# logic.net
KiCad netlist of a schematic drawn in EAGLE
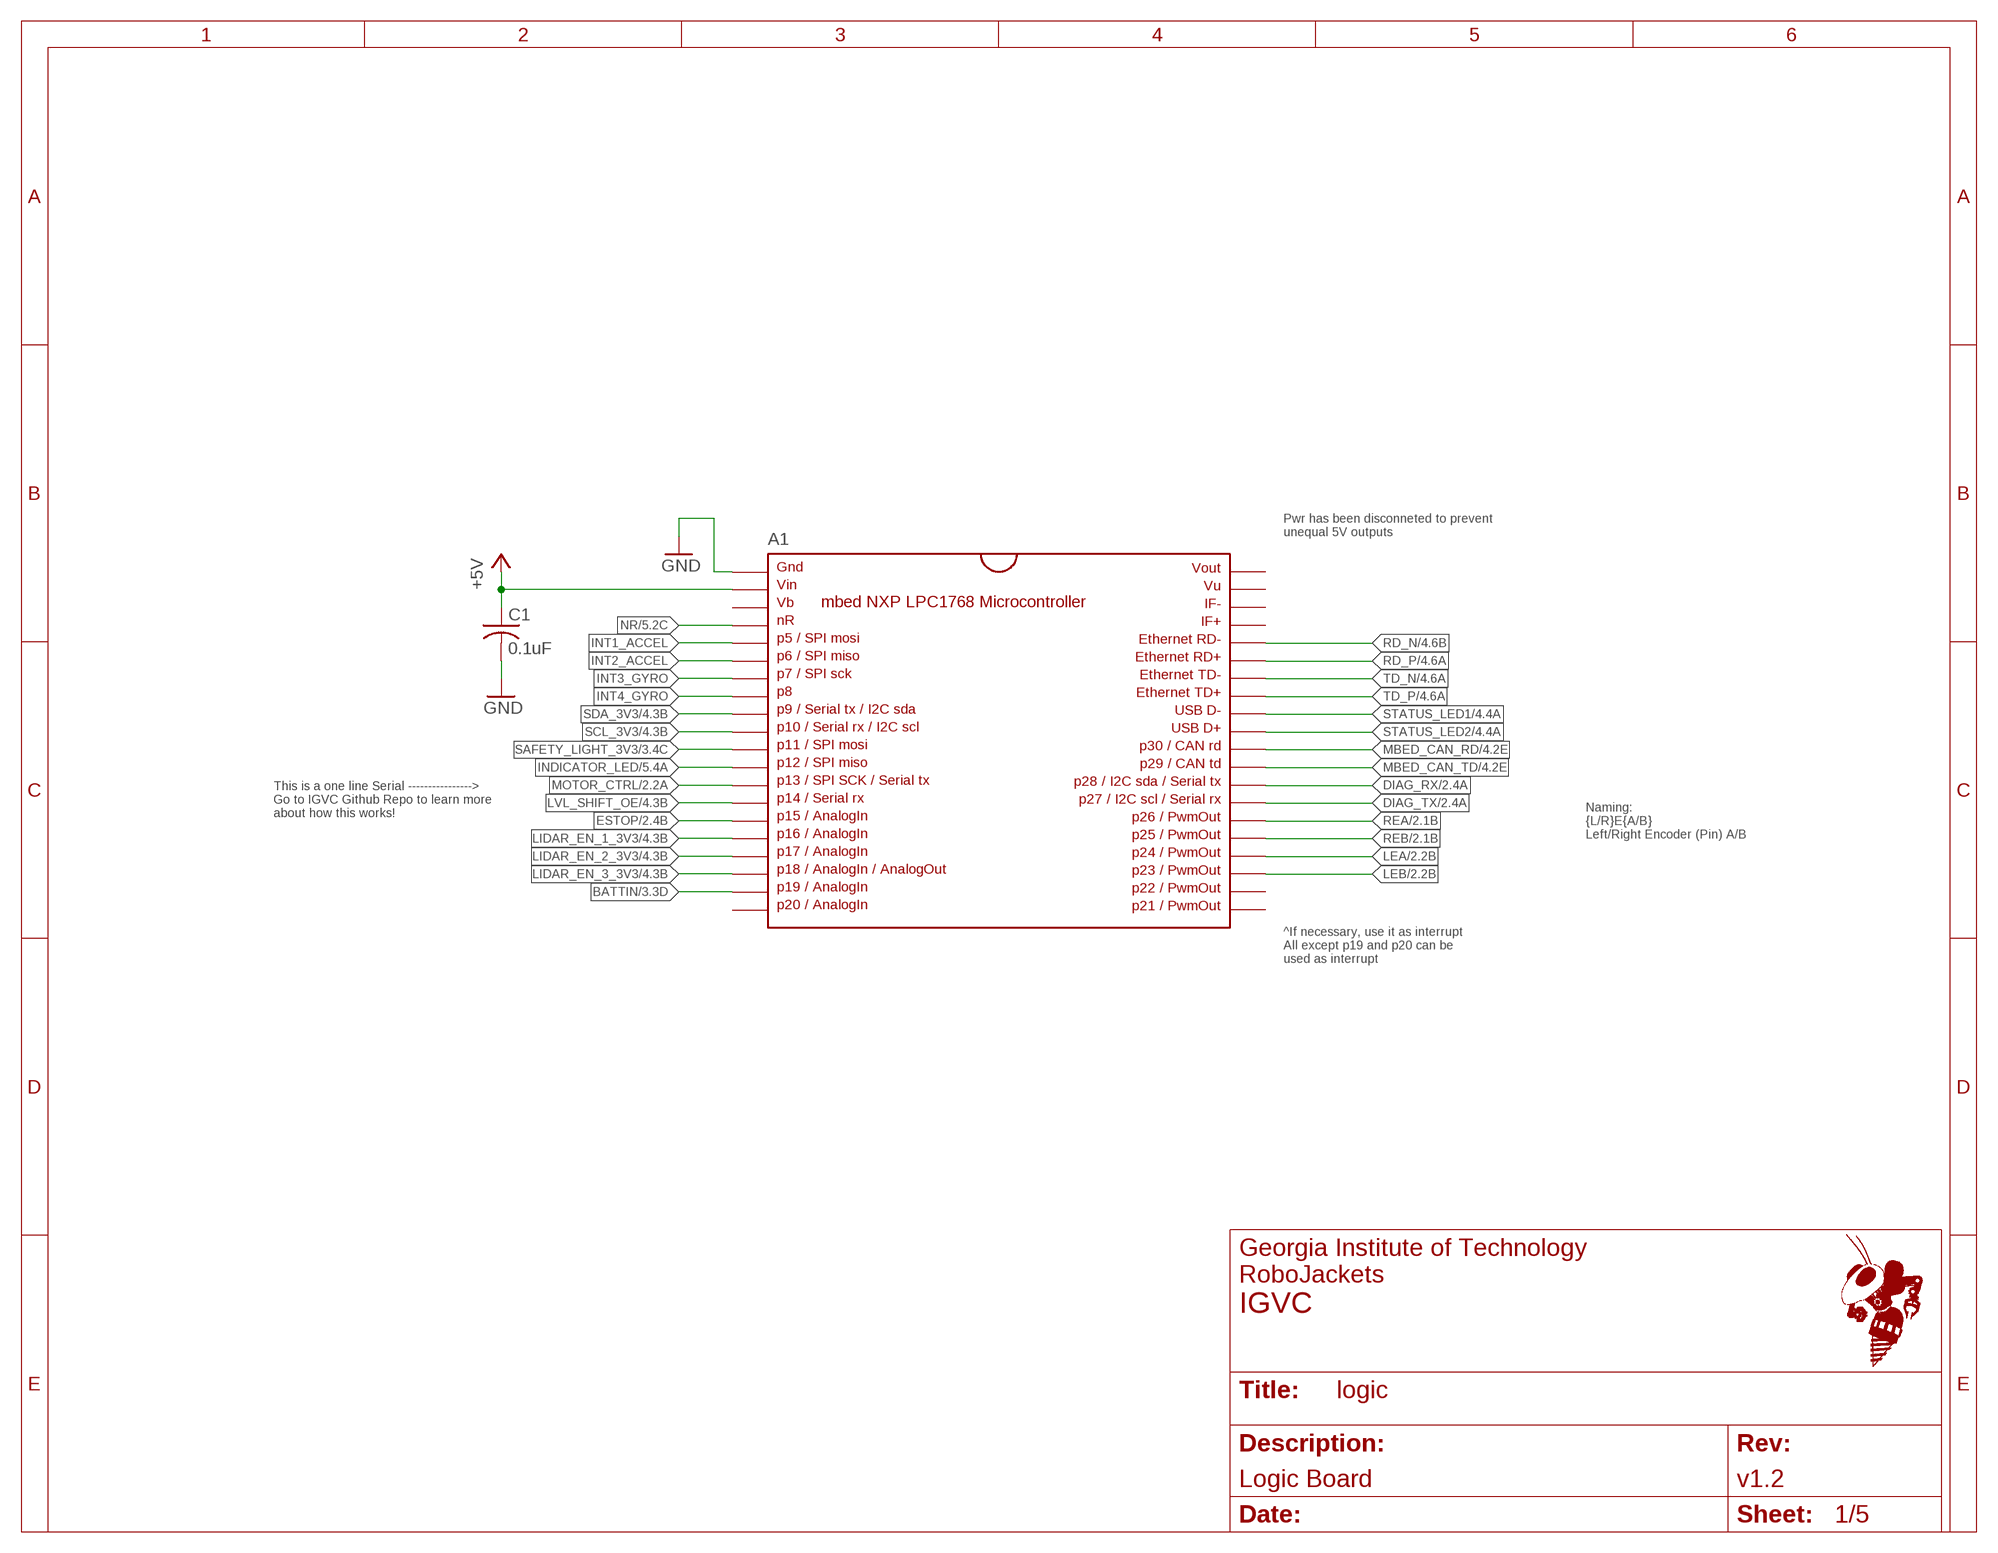
[diagram p0: schematic, sheet 1]
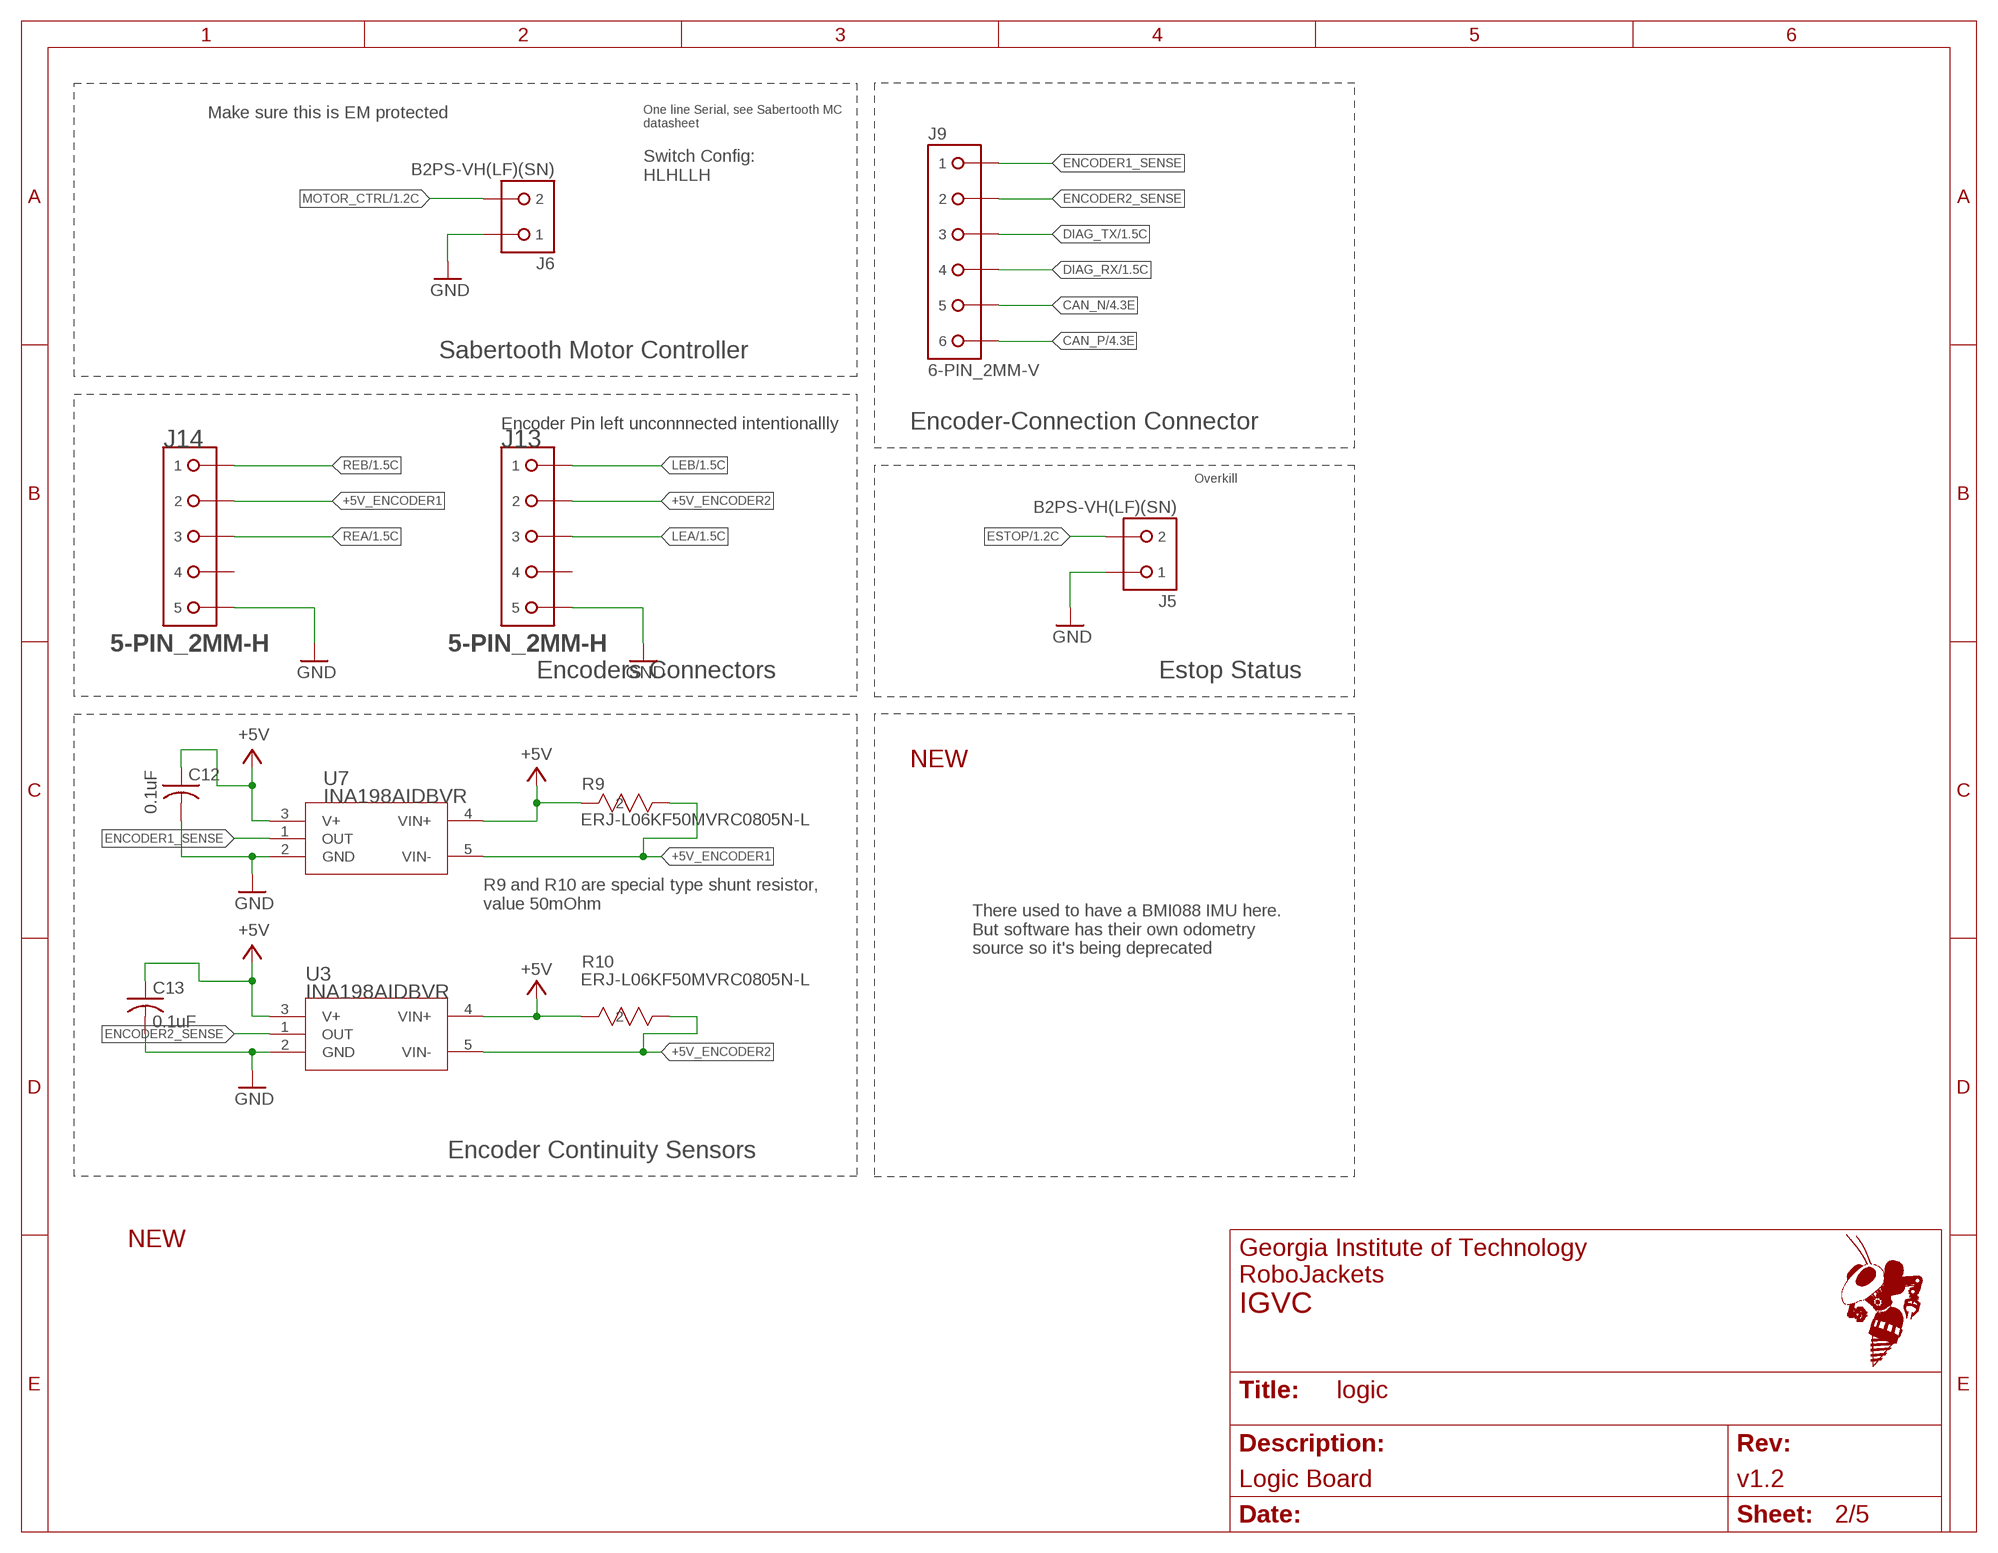
[diagram p1: schematic, sheet 2]
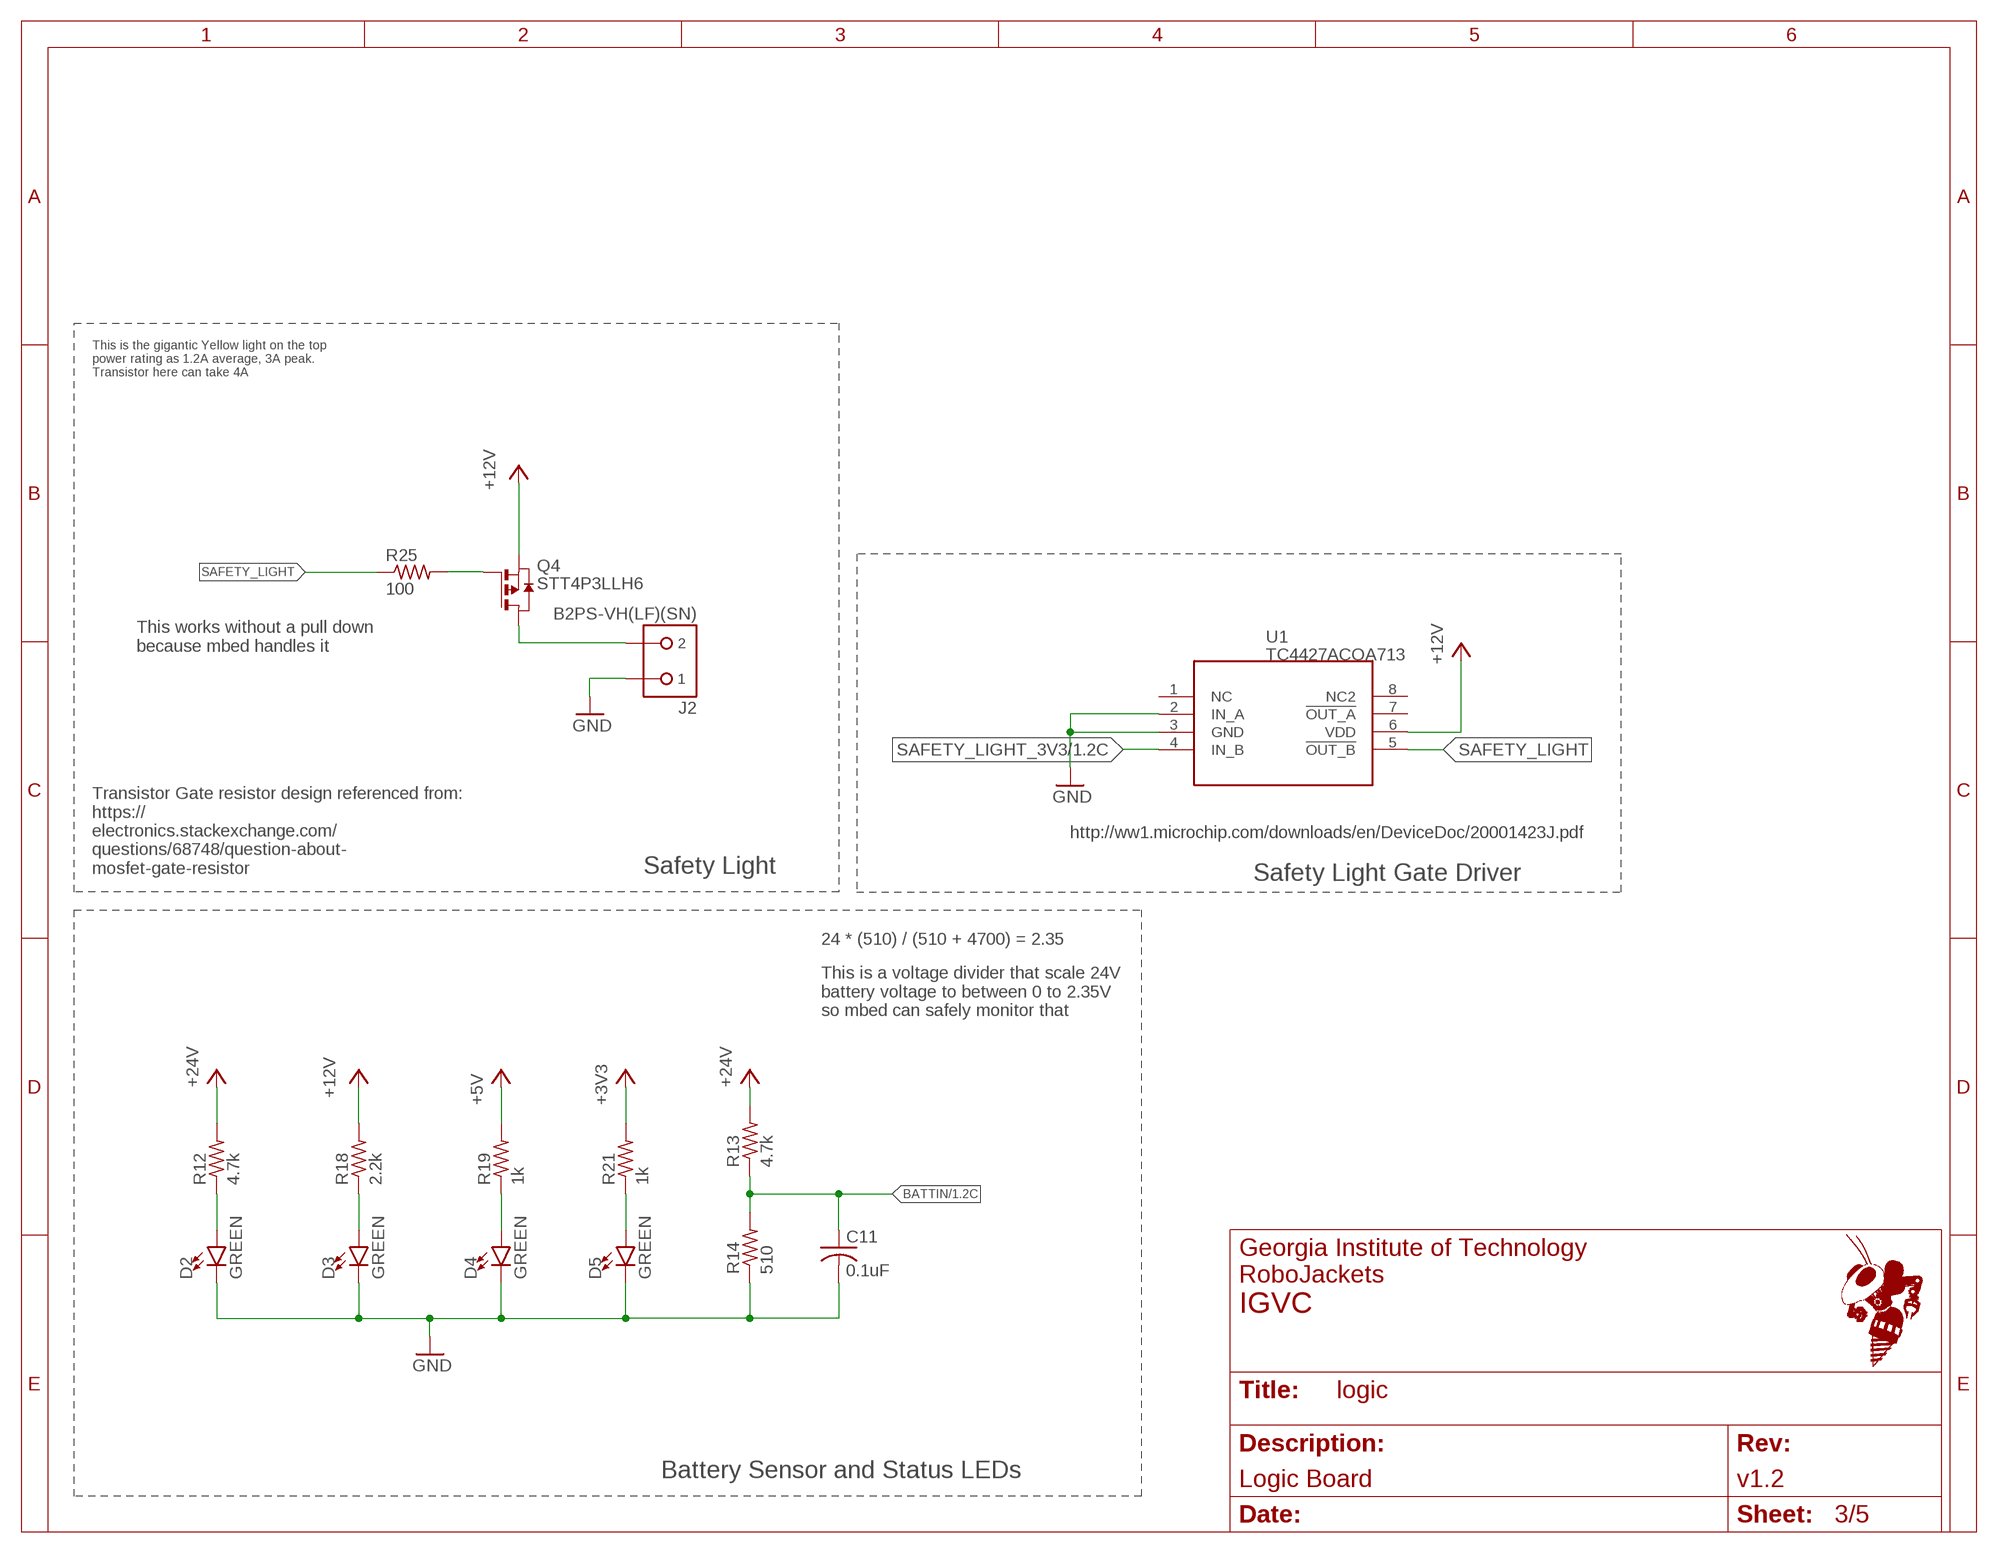
[diagram p2: schematic, sheet 3]
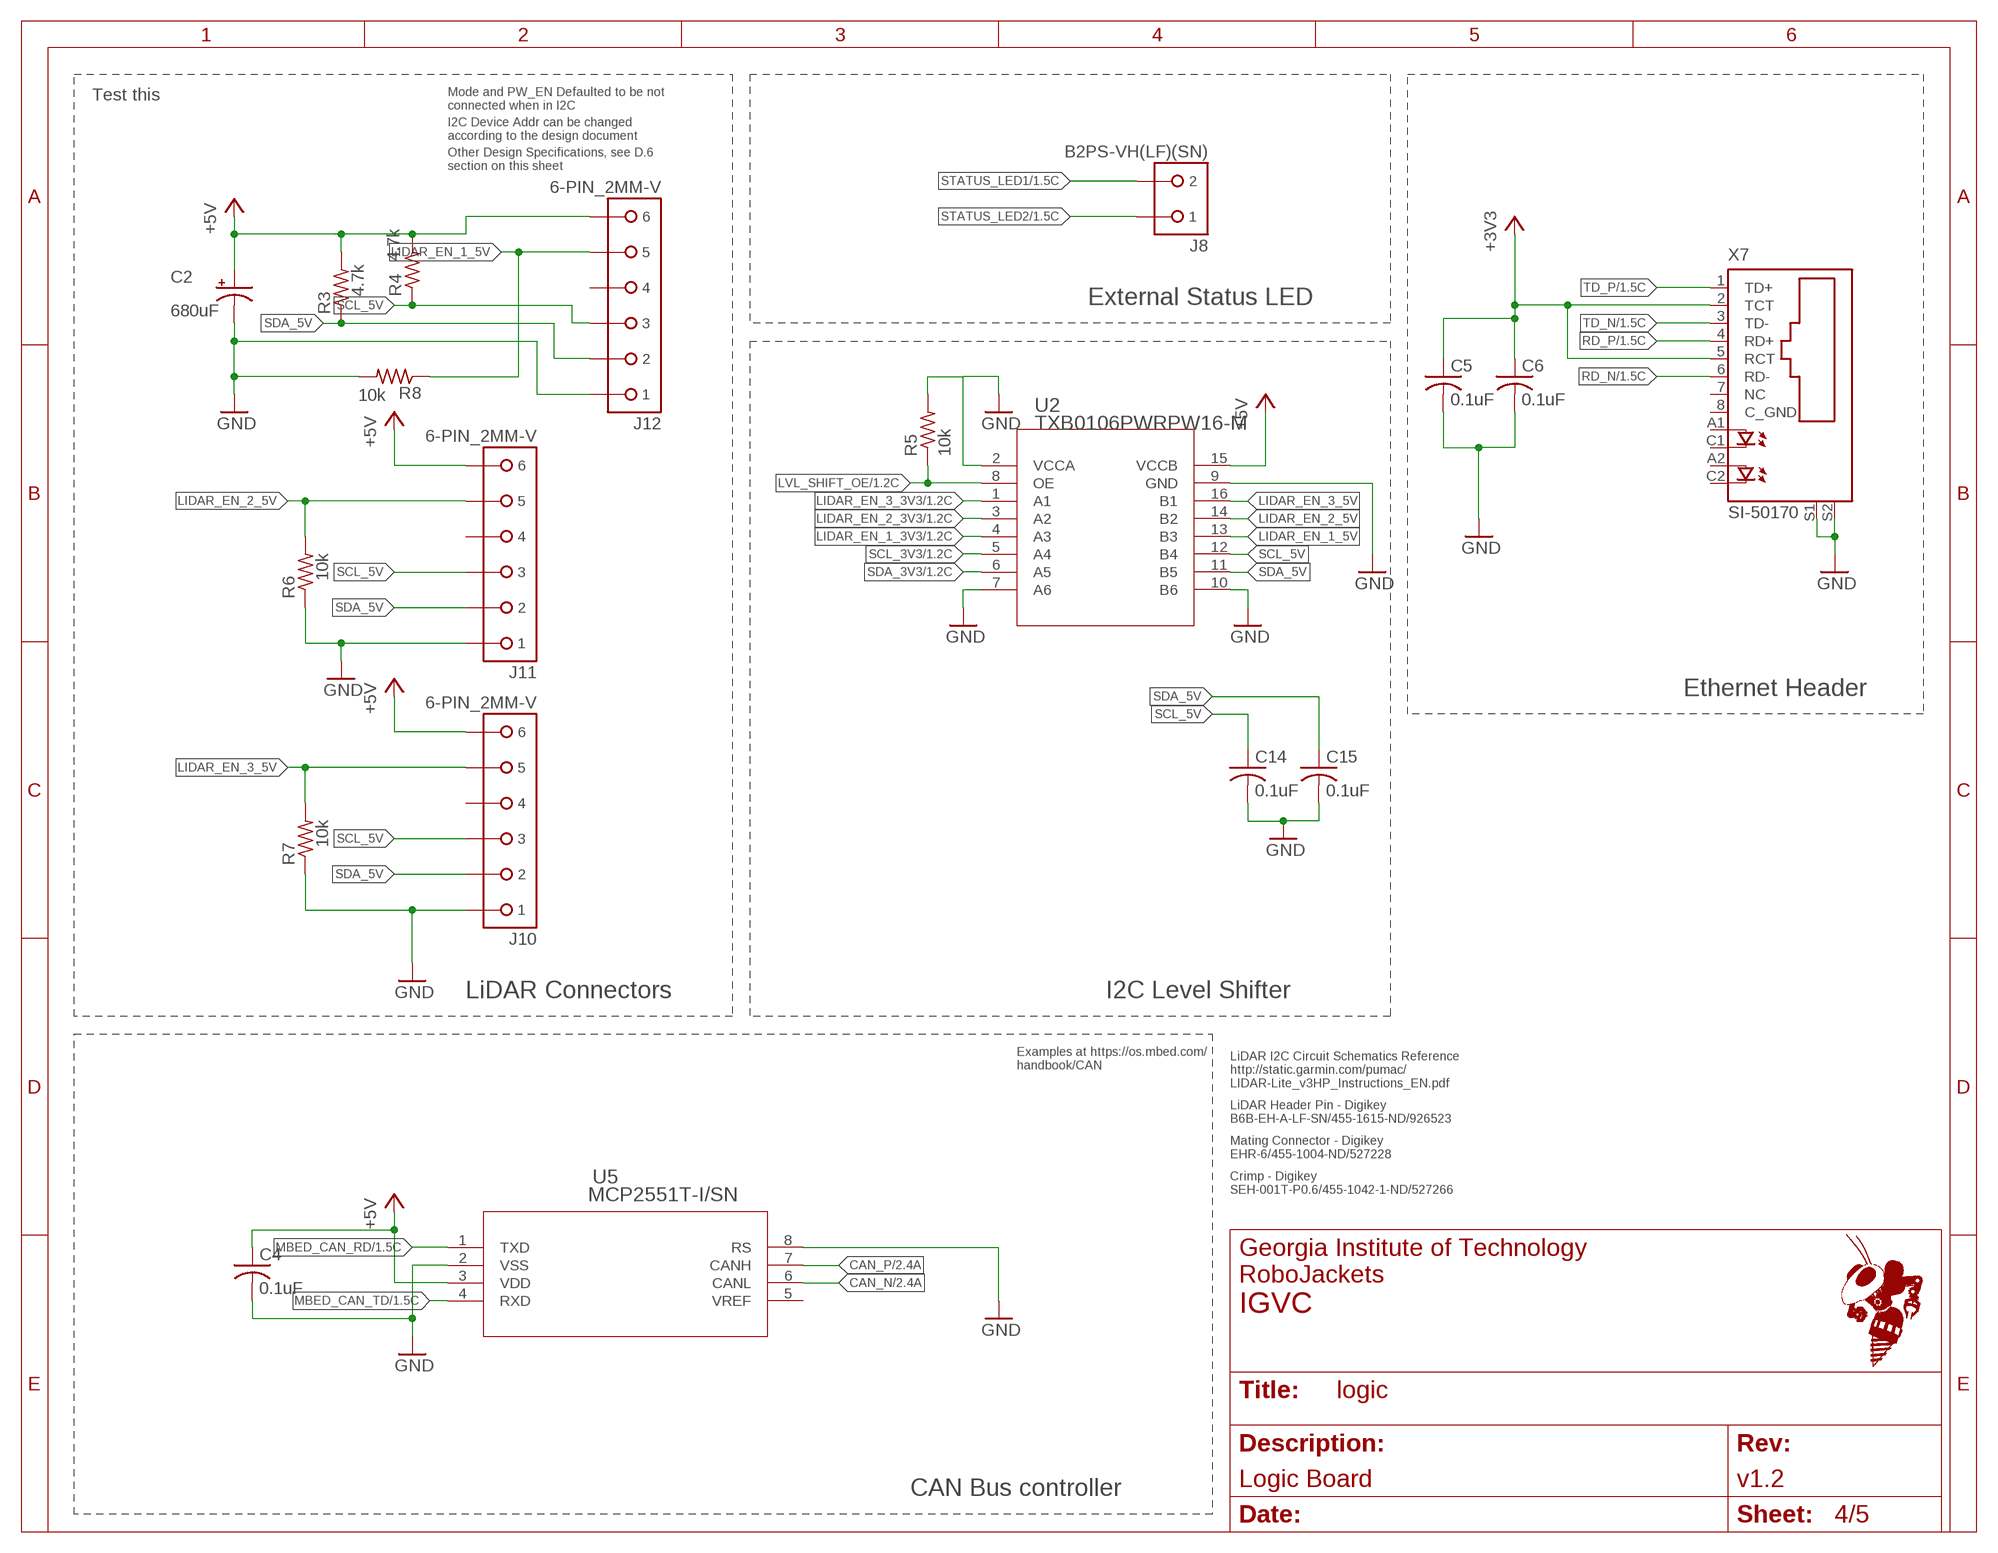
[diagram p3: schematic, sheet 4]
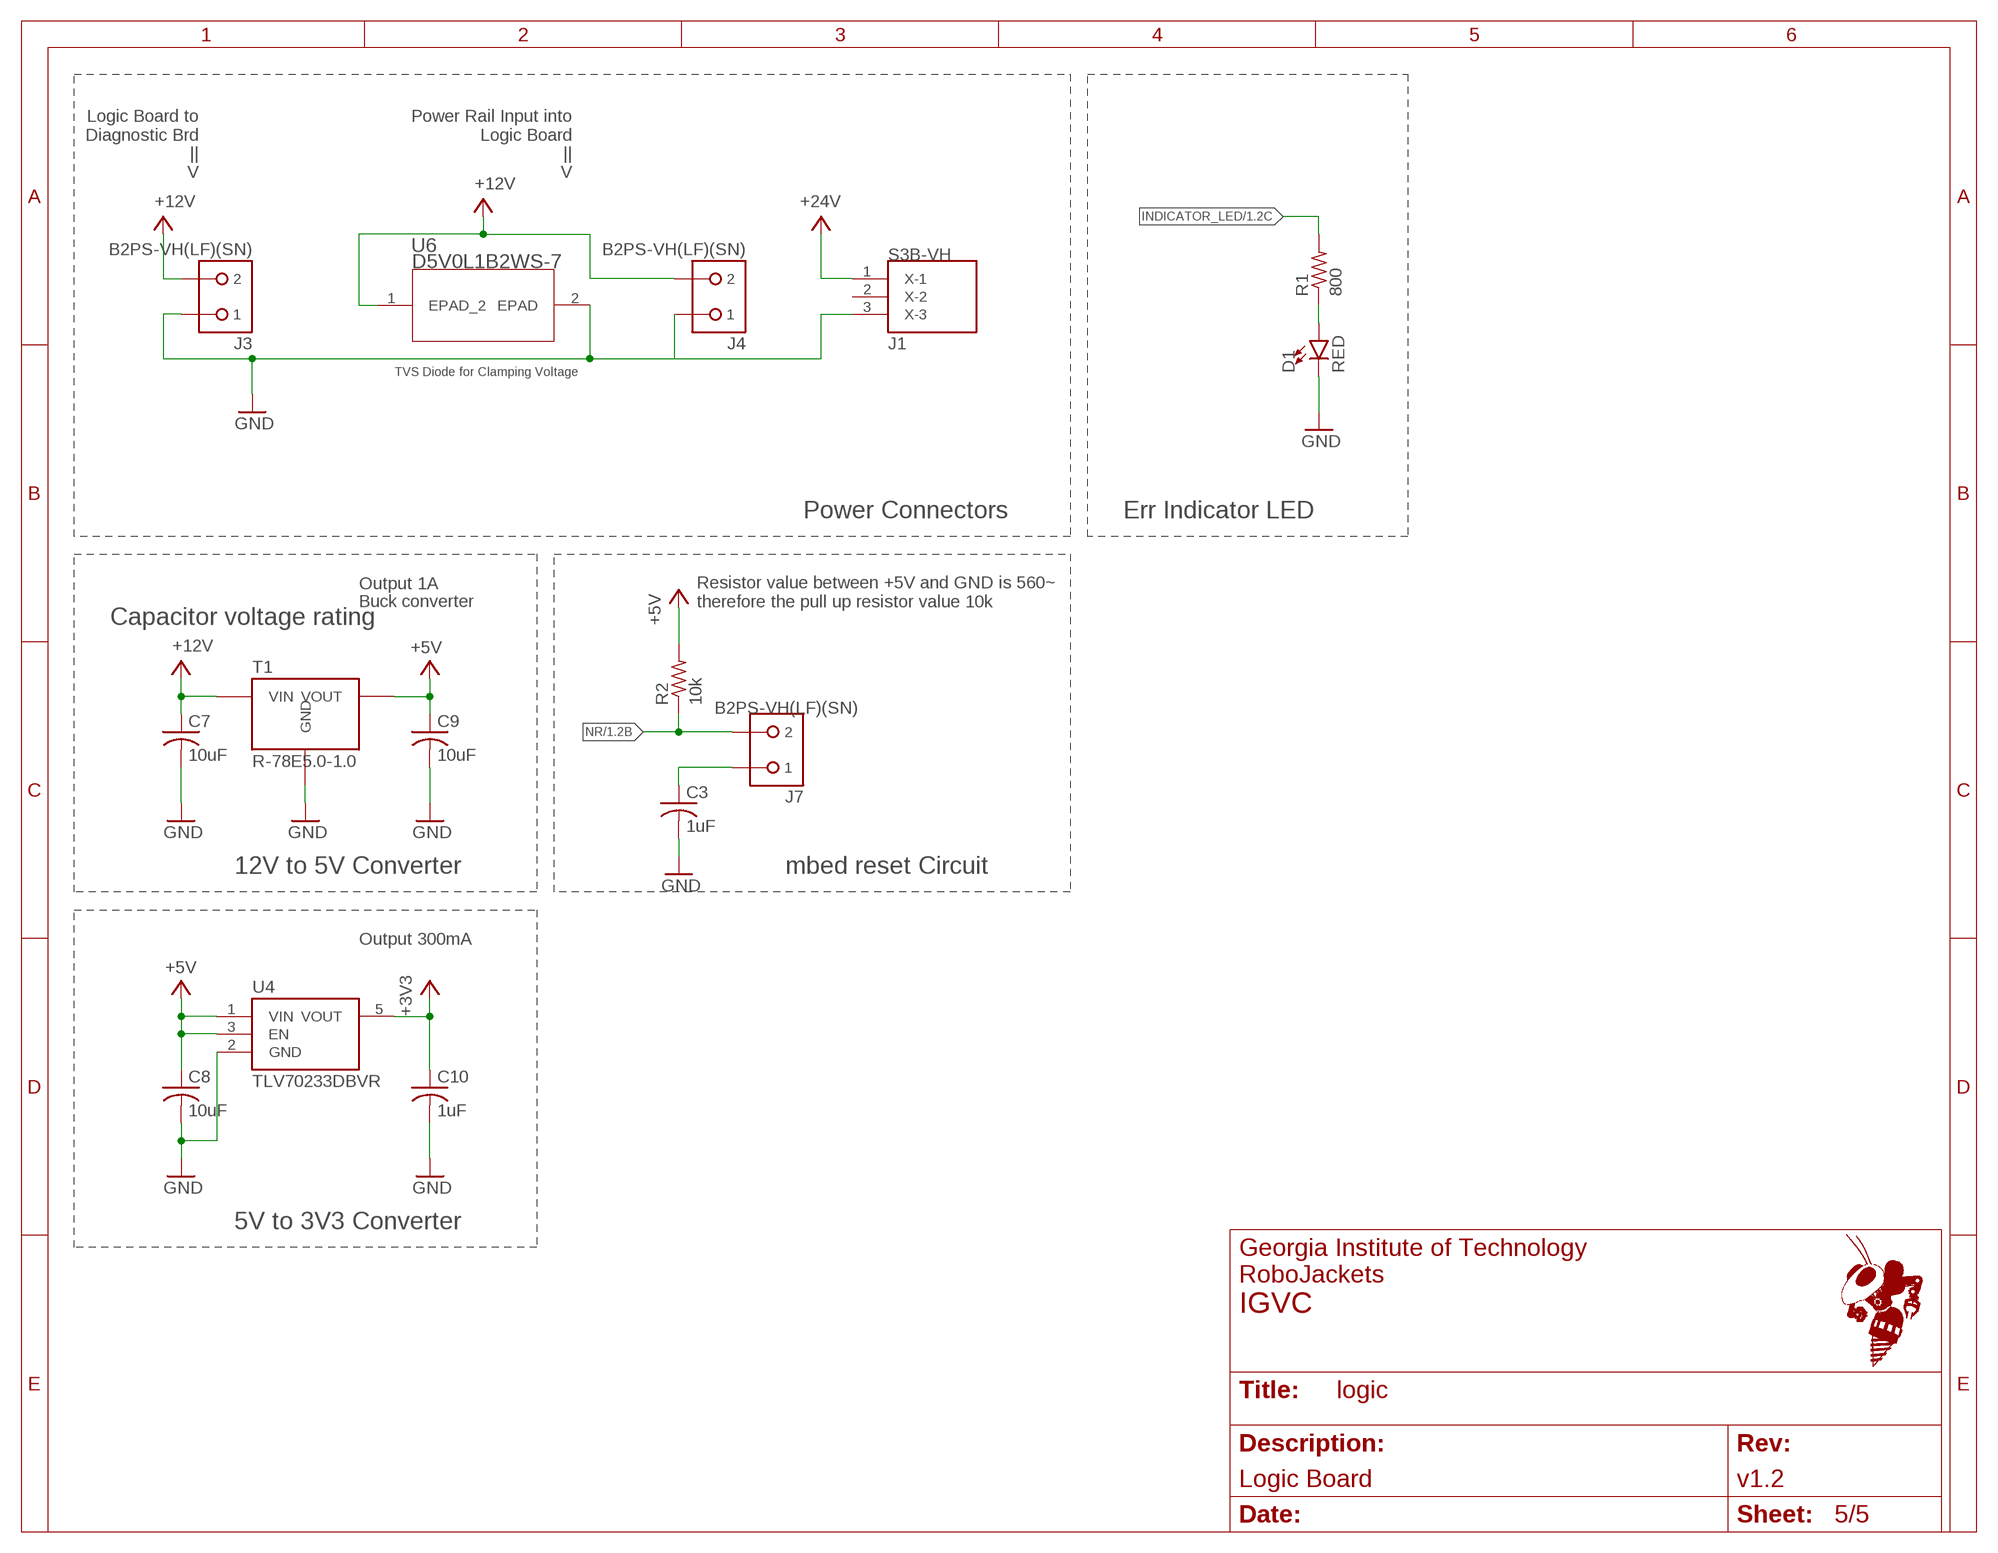
[diagram p4: schematic, sheet 5]

(export (version "E")
  (design (tool "Eeschema 10.0.6"))
  (components
    (comp (ref "A1")
      (value "MBED1768")
      (footprint "eagle-import:SPARKFUN-BOARDS_DIL40_0.9")
      (libsource (lib "eagle-import") (part "SPARKFUN-BOARDS_MBED_NXP_LPC1768"))
    )
    (comp (ref "C1")
      (value "0.1uF")
      (footprint "eagle-import:C0603")
      (libsource (lib "eagle-import") (part "C-USC0603"))
    )
    (comp (ref "C11")
      (value "0.1uF")
      (footprint "eagle-import:C0603")
      (libsource (lib "eagle-import") (part "C-USC0603"))
    )
    (comp (ref "D2")
      (value "GREEN")
      (footprint "eagle-import:LED-0603")
      (libsource (lib "eagle-import") (part "LED-BLUE0603"))
    )
    (comp (ref "D3")
      (value "GREEN")
      (footprint "eagle-import:LED-0603")
      (libsource (lib "eagle-import") (part "LED-BLUE0603"))
    )
    (comp (ref "D4")
      (value "GREEN")
      (footprint "eagle-import:LED-0603")
      (libsource (lib "eagle-import") (part "LED-GREEN0603"))
    )
    (comp (ref "D5")
      (value "GREEN")
      (footprint "eagle-import:LED-0603")
      (libsource (lib "eagle-import") (part "LED-GREEN0603"))
    )
    (comp (ref "J2")
      (value "B2PS-VH(LF)(SN)")
      (footprint "eagle-import:B2PS-CENTERED")
      (libsource (lib "eagle-import") (part "B2P?-VH(LF)(SN)S"))
    )
    (comp (ref "Q4")
      (value "STT4P3LLH6")
      (footprint "eagle-import:SOT23-6")
      (libsource (lib "eagle-import") (part "STT4P3LLH6"))
    )
    (comp (ref "R12")
      (value "4.7k")
      (footprint "eagle-import:R0603")
      (libsource (lib "eagle-import") (part "R-US_R0603"))
    )
    (comp (ref "R13")
      (value "4.7k")
      (footprint "eagle-import:R0603")
      (libsource (lib "eagle-import") (part "R-US_R0603"))
    )
    (comp (ref "R14")
      (value "510")
      (footprint "eagle-import:R0603")
      (libsource (lib "eagle-import") (part "R-US_R0603"))
    )
    (comp (ref "R18")
      (value "2.2k")
      (footprint "eagle-import:R0603")
      (libsource (lib "eagle-import") (part "R-US_R0603"))
    )
    (comp (ref "R19")
      (value "1k")
      (footprint "eagle-import:R0603")
      (libsource (lib "eagle-import") (part "R-US_R0603"))
    )
    (comp (ref "R21")
      (value "1k")
      (footprint "eagle-import:R0603")
      (libsource (lib "eagle-import") (part "R-US_R0603"))
    )
    (comp (ref "R25")
      (value "100")
      (footprint "eagle-import:R0603")
      (libsource (lib "eagle-import") (part "R-US_R0603"))
    )
    (comp (ref "U1")
      (value "TC4427ACOA713")
      (footprint "eagle-import:SOIC-8")
      (libsource (lib "eagle-import") (part "TC4427ACOA713"))
    )
    (comp (ref "C12")
      (value "0.1uF")
      (footprint "eagle-import:C0603")
      (libsource (lib "eagle-import") (part "C-USC0603"))
    )
    (comp (ref "C13")
      (value "0.1uF")
      (footprint "eagle-import:C0603")
      (libsource (lib "eagle-import") (part "C-USC0603"))
    )
    (comp (ref "J5")
      (value "B2PS-VH(LF)(SN)")
      (footprint "eagle-import:B2PS-CENTERED")
      (libsource (lib "eagle-import") (part "B2P?-VH(LF)(SN)S"))
    )
    (comp (ref "J6")
      (value "B2PS-VH(LF)(SN)")
      (footprint "eagle-import:B2PS-CENTERED")
      (libsource (lib "eagle-import") (part "B2P?-VH(LF)(SN)S"))
    )
    (comp (ref "J9")
      (value "6-PIN_2MM-V")
      (footprint "eagle-import:2MM-6-V")
      (libsource (lib "eagle-import") (part "6-PIN_2MM-V"))
    )
    (comp (ref "J13")
      (value "5-PIN_2MM-H")
      (footprint "eagle-import:2MM-5-H")
      (libsource (lib "eagle-import") (part "5-PIN_2MM-H"))
    )
    (comp (ref "J14")
      (value "5-PIN_2MM-H")
      (footprint "eagle-import:2MM-5-H")
      (libsource (lib "eagle-import") (part "5-PIN_2MM-H"))
    )
    (comp (ref "R9")
      (value "ERJ-L06KF50MVRC0805N-L")
      (footprint "eagle-import:RC0805N-L")
      (fields (field (name "MANUFACTURER_PART_NUMBER") "ERJL06KF50MV"))
      (libsource (lib "eagle-import") (part "ERJ-L06KF50MVRC0805N-L"))
    )
    (comp (ref "R10")
      (value "ERJ-L06KF50MVRC0805N-L")
      (footprint "eagle-import:RC0805N-L")
      (fields (field (name "MANUFACTURER_PART_NUMBER") "ERJL06KF50MV"))
      (libsource (lib "eagle-import") (part "ERJ-L06KF50MVRC0805N-L"))
    )
    (comp (ref "U3")
      (value "INA198AIDBVR")
      (footprint "eagle-import:DBV5")
      (libsource (lib "eagle-import") (part "INA198AIDBVR"))
    )
    (comp (ref "U7")
      (value "INA198AIDBVR")
      (footprint "eagle-import:DBV5")
      (libsource (lib "eagle-import") (part "INA198AIDBVR"))
    )
    (comp (ref "C2")
      (value "680uF")
      (footprint "eagle-import:E5-5")
      (libsource (lib "eagle-import") (part "CPOL-USE5-5"))
    )
    (comp (ref "C4")
      (value "0.1uF")
      (footprint "eagle-import:C0603")
      (libsource (lib "eagle-import") (part "C-USC0603"))
    )
    (comp (ref "C5")
      (value "0.1uF")
      (footprint "eagle-import:C0603")
      (libsource (lib "eagle-import") (part "C-USC0603"))
    )
    (comp (ref "C6")
      (value "0.1uF")
      (footprint "eagle-import:C0603")
      (libsource (lib "eagle-import") (part "C-USC0603"))
    )
    (comp (ref "C14")
      (value "0.1uF")
      (footprint "eagle-import:C0603")
      (libsource (lib "eagle-import") (part "C-USC0603"))
    )
    (comp (ref "C15")
      (value "0.1uF")
      (footprint "eagle-import:C0603")
      (libsource (lib "eagle-import") (part "C-USC0603"))
    )
    (comp (ref "J8")
      (value "B2PS-VH(LF)(SN)")
      (footprint "eagle-import:B2PS-CENTERED")
      (libsource (lib "eagle-import") (part "B2P?-VH(LF)(SN)S"))
    )
    (comp (ref "J10")
      (value "6-PIN_2MM-V")
      (footprint "eagle-import:2MM-6-V")
      (libsource (lib "eagle-import") (part "6-PIN_2MM-V"))
    )
    (comp (ref "J11")
      (value "6-PIN_2MM-V")
      (footprint "eagle-import:2MM-6-V")
      (libsource (lib "eagle-import") (part "6-PIN_2MM-V"))
    )
    (comp (ref "J12")
      (value "6-PIN_2MM-V")
      (footprint "eagle-import:2MM-6-V")
      (libsource (lib "eagle-import") (part "6-PIN_2MM-V"))
    )
    (comp (ref "R3")
      (value "4.7k")
      (footprint "eagle-import:R0603")
      (libsource (lib "eagle-import") (part "R-US_R0603"))
    )
    (comp (ref "R4")
      (value "4.7k")
      (footprint "eagle-import:R0603")
      (libsource (lib "eagle-import") (part "R-US_R0603"))
    )
    (comp (ref "R5")
      (value "10k")
      (footprint "eagle-import:R0603")
      (libsource (lib "eagle-import") (part "R-US_R0603"))
    )
    (comp (ref "R6")
      (value "10k")
      (footprint "eagle-import:R0603")
      (libsource (lib "eagle-import") (part "R-US_R0603"))
    )
    (comp (ref "R7")
      (value "10k")
      (footprint "eagle-import:R0603")
      (libsource (lib "eagle-import") (part "R-US_R0603"))
    )
    (comp (ref "R8")
      (value "10k")
      (footprint "eagle-import:R0603")
      (libsource (lib "eagle-import") (part "R-US_R0603"))
    )
    (comp (ref "U2")
      (value "TXB0106PWRPW16-M")
      (footprint "eagle-import:PW16-M")
      (fields (field (name "MANUFACTURER_PART_NUMBER") "TXB0106PWR"))
      (libsource (lib "eagle-import") (part "TXB0106PWRPW16-M"))
    )
    (comp (ref "U5")
      (value "MCP2551T-I/SN")
      (footprint "eagle-import:SOIC8-N_MC")
      (fields (field (name "MANUFACTURER_PART_NUMBER") "MCP2551TISN"))
      (libsource (lib "eagle-import") (part "MCP2551T-I/SN"))
    )
    (comp (ref "X7")
      (value "SI-50170")
      (footprint "eagle-import:SI-50170")
      (libsource (lib "eagle-import") (part "SI-50170"))
    )
    (comp (ref "C3")
      (value "1uF")
      (footprint "eagle-import:C0805")
      (libsource (lib "eagle-import") (part "C-USC0805"))
    )
    (comp (ref "C7")
      (value "10uF")
      (footprint "eagle-import:C0805")
      (libsource (lib "eagle-import") (part "C-USC0805"))
    )
    (comp (ref "C8")
      (value "10uF")
      (footprint "eagle-import:C0805")
      (libsource (lib "eagle-import") (part "C-USC0805"))
    )
    (comp (ref "C9")
      (value "10uF")
      (footprint "eagle-import:C0805")
      (libsource (lib "eagle-import") (part "C-USC0805"))
    )
    (comp (ref "C10")
      (value "1uF")
      (footprint "eagle-import:C0805")
      (libsource (lib "eagle-import") (part "C-USC0805"))
    )
    (comp (ref "D1")
      (value "RED")
      (footprint "eagle-import:LED-0603")
      (libsource (lib "eagle-import") (part "LED-BLUE0603"))
    )
    (comp (ref "J1")
      (value "S3B-VH")
      (footprint "eagle-import:S3B-VH")
      (libsource (lib "eagle-import") (part "S3B-VH"))
    )
    (comp (ref "J3")
      (value "B2PS-VH(LF)(SN)")
      (footprint "eagle-import:B2PS-CENTERED")
      (libsource (lib "eagle-import") (part "B2P?-VH(LF)(SN)S"))
    )
    (comp (ref "J4")
      (value "B2PS-VH(LF)(SN)")
      (footprint "eagle-import:B2PS-CENTERED")
      (libsource (lib "eagle-import") (part "B2P?-VH(LF)(SN)S"))
    )
    (comp (ref "J7")
      (value "B2PS-VH(LF)(SN)")
      (footprint "eagle-import:B2PS-CENTERED")
      (libsource (lib "eagle-import") (part "B2P?-VH(LF)(SN)S"))
    )
    (comp (ref "R1")
      (value "800")
      (footprint "eagle-import:R0603")
      (libsource (lib "eagle-import") (part "R-US_R0603"))
    )
    (comp (ref "R2")
      (value "10k")
      (footprint "eagle-import:R0603")
      (libsource (lib "eagle-import") (part "R-US_R0603"))
    )
    (comp (ref "T1")
      (value "R-78E5.0-1.0")
      (footprint "eagle-import:R-78E")
      (libsource (lib "eagle-import") (part "R-78E5.0-1.0"))
    )
    (comp (ref "U4")
      (value "TLV70233DBVR")
      (footprint "eagle-import:SOT-23-5")
      (libsource (lib "eagle-import") (part "TLV70233DBVR"))
    )
    (comp (ref "U6")
      (value "D5V0L1B2WS-7")
      (footprint "eagle-import:SOD323")
      (libsource (lib "eagle-import") (part "D5V0L1B2WS-7"))
    )
  )
  (nets
    (net (code "1") (name "+3V3") (class "Default")
      (node (ref "C10") (pin "1") (pinfunction "1_1") (pintype "passive"))
      (node (ref "C5") (pin "1") (pinfunction "1_1") (pintype "passive"))
      (node (ref "C6") (pin "1") (pinfunction "1_1") (pintype "passive"))
      (node (ref "R21") (pin "2") (pinfunction "2_2") (pintype "passive"))
      (node (ref "U4") (pin "5") (pinfunction "VOUT_5") (pintype "bidirectional"))
      (node (ref "X7") (pin "2") (pinfunction "TCT_2") (pintype "passive"))
      (node (ref "X7") (pin "5") (pinfunction "RCT_5") (pintype "passive"))
    )
    (net (code "2") (name "+5V") (class "Default")
      (node (ref "A1") (pin "2") (pinfunction "P$2_2") (pintype "bidirectional"))
      (node (ref "C1") (pin "1") (pinfunction "1_1") (pintype "passive"))
      (node (ref "C12") (pin "1") (pinfunction "1_1") (pintype "passive"))
      (node (ref "C13") (pin "1") (pinfunction "1_1") (pintype "passive"))
      (node (ref "C2") (pin "+") (pinfunction "+_+") (pintype "passive"))
      (node (ref "C4") (pin "1") (pinfunction "1_1") (pintype "passive"))
      (node (ref "C8") (pin "1") (pinfunction "1_1") (pintype "passive"))
      (node (ref "C9") (pin "1") (pinfunction "1_1") (pintype "passive"))
      (node (ref "J10") (pin "6") (pinfunction "6_6") (pintype "passive"))
      (node (ref "J11") (pin "6") (pinfunction "6_6") (pintype "passive"))
      (node (ref "J12") (pin "6") (pinfunction "6_6") (pintype "passive"))
      (node (ref "R10") (pin "2") (pinfunction "2_2") (pintype "passive"))
      (node (ref "R19") (pin "2") (pinfunction "2_2") (pintype "passive"))
      (node (ref "R2") (pin "2") (pinfunction "2_2") (pintype "passive"))
      (node (ref "R3") (pin "2") (pinfunction "2_2") (pintype "passive"))
      (node (ref "R4") (pin "2") (pinfunction "2_2") (pintype "passive"))
      (node (ref "R9") (pin "2") (pinfunction "2_2") (pintype "passive"))
      (node (ref "T1") (pin "3") (pinfunction "VOUT_3") (pintype "bidirectional"))
      (node (ref "U2") (pin "15") (pinfunction "VCCB_15") (pintype "power_in"))
      (node (ref "U3") (pin "3") (pinfunction "V+_3") (pintype "power_in"))
      (node (ref "U3") (pin "4") (pinfunction "VIN+_4") (pintype "input"))
      (node (ref "U4") (pin "1") (pinfunction "VIN_1") (pintype "bidirectional"))
      (node (ref "U4") (pin "3") (pinfunction "EN_3") (pintype "bidirectional"))
      (node (ref "U5") (pin "3") (pinfunction "VDD_3") (pintype "passive"))
      (node (ref "U7") (pin "3") (pinfunction "V+_3") (pintype "power_in"))
      (node (ref "U7") (pin "4") (pinfunction "VIN+_4") (pintype "input"))
    )
    (net (code "3") (name "+5V_ENCODER1") (class "Default")
      (node (ref "J14") (pin "2") (pinfunction "2_2") (pintype "passive"))
      (node (ref "R9") (pin "1") (pinfunction "1_1") (pintype "passive"))
      (node (ref "U7") (pin "5") (pinfunction "VIN-_5") (pintype "input"))
    )
    (net (code "4") (name "+5V_ENCODER2") (class "Default")
      (node (ref "J13") (pin "2") (pinfunction "2_2") (pintype "passive"))
      (node (ref "R10") (pin "1") (pinfunction "1_1") (pintype "passive"))
      (node (ref "U3") (pin "5") (pinfunction "VIN-_5") (pintype "input"))
    )
    (net (code "5") (name "+12V") (class "Default")
      (node (ref "C7") (pin "1") (pinfunction "1_1") (pintype "passive"))
      (node (ref "J3") (pin "2") (pinfunction "2_2") (pintype "bidirectional"))
      (node (ref "J4") (pin "2") (pinfunction "2_2") (pintype "bidirectional"))
      (node (ref "Q4") (pin "4") (pinfunction "S_4") (pintype "passive"))
      (node (ref "R18") (pin "2") (pinfunction "2_2") (pintype "passive"))
      (node (ref "T1") (pin "1") (pinfunction "VIN_1") (pintype "bidirectional"))
      (node (ref "U1") (pin "6") (pinfunction "VDD_6") (pintype "bidirectional"))
      (node (ref "U6") (pin "1") (pinfunction "EPAD_2_1") (pintype "passive"))
    )
    (net (code "6") (name "+24V") (class "Default")
      (node (ref "J1") (pin "1") (pinfunction "X-1_1") (pintype "bidirectional"))
      (node (ref "R12") (pin "2") (pinfunction "2_2") (pintype "passive"))
      (node (ref "R13") (pin "2") (pinfunction "2_2") (pintype "passive"))
    )
    (net (code "7") (name "BATTIN") (class "Default")
      (node (ref "A1") (pin "19") (pinfunction "P$19_19") (pintype "bidirectional"))
      (node (ref "C11") (pin "1") (pinfunction "1_1") (pintype "passive"))
      (node (ref "R13") (pin "1") (pinfunction "1_1") (pintype "passive"))
      (node (ref "R14") (pin "2") (pinfunction "2_2") (pintype "passive"))
    )
    (net (code "8") (name "CAN_N") (class "Default")
      (node (ref "J9") (pin "5") (pinfunction "5_5") (pintype "passive"))
      (node (ref "U5") (pin "6") (pinfunction "CANL_6") (pintype "passive"))
    )
    (net (code "9") (name "CAN_P") (class "Default")
      (node (ref "J9") (pin "6") (pinfunction "6_6") (pintype "passive"))
      (node (ref "U5") (pin "7") (pinfunction "CANH_7") (pintype "passive"))
    )
    (net (code "10") (name "DIAG_RX") (class "Default")
      (node (ref "A1") (pin "28") (pinfunction "P$28_28") (pintype "bidirectional"))
      (node (ref "J9") (pin "4") (pinfunction "4_4") (pintype "passive"))
    )
    (net (code "11") (name "DIAG_TX") (class "Default")
      (node (ref "A1") (pin "27") (pinfunction "P$27_27") (pintype "bidirectional"))
      (node (ref "J9") (pin "3") (pinfunction "3_3") (pintype "passive"))
    )
    (net (code "12") (name "ENCODER1_SENSE") (class "Default")
      (node (ref "J9") (pin "1") (pinfunction "1_1") (pintype "passive"))
      (node (ref "U7") (pin "1") (pinfunction "OUT_1") (pintype "output"))
    )
    (net (code "13") (name "ENCODER2_SENSE") (class "Default")
      (node (ref "J9") (pin "2") (pinfunction "2_2") (pintype "passive"))
      (node (ref "U3") (pin "1") (pinfunction "OUT_1") (pintype "output"))
    )
    (net (code "14") (name "ESTOP") (class "Default")
      (node (ref "A1") (pin "15") (pinfunction "P$15_15") (pintype "bidirectional"))
      (node (ref "J5") (pin "2") (pinfunction "2_2") (pintype "bidirectional"))
    )
    (net (code "15") (name "GND") (class "Default")
      (node (ref "A1") (pin "1") (pinfunction "P$1_1") (pintype "bidirectional"))
      (node (ref "C1") (pin "2") (pinfunction "2_2") (pintype "passive"))
      (node (ref "C10") (pin "2") (pinfunction "2_2") (pintype "passive"))
      (node (ref "C11") (pin "2") (pinfunction "2_2") (pintype "passive"))
      (node (ref "C12") (pin "2") (pinfunction "2_2") (pintype "passive"))
      (node (ref "C13") (pin "2") (pinfunction "2_2") (pintype "passive"))
      (node (ref "C14") (pin "2") (pinfunction "2_2") (pintype "passive"))
      (node (ref "C15") (pin "2") (pinfunction "2_2") (pintype "passive"))
      (node (ref "C2") (pin "-") (pinfunction "-_-") (pintype "passive"))
      (node (ref "C3") (pin "2") (pinfunction "2_2") (pintype "passive"))
      (node (ref "C4") (pin "2") (pinfunction "2_2") (pintype "passive"))
      (node (ref "C5") (pin "2") (pinfunction "2_2") (pintype "passive"))
      (node (ref "C6") (pin "2") (pinfunction "2_2") (pintype "passive"))
      (node (ref "C7") (pin "2") (pinfunction "2_2") (pintype "passive"))
      (node (ref "C8") (pin "2") (pinfunction "2_2") (pintype "passive"))
      (node (ref "C9") (pin "2") (pinfunction "2_2") (pintype "passive"))
      (node (ref "D1") (pin "C") (pinfunction "C_C") (pintype "passive"))
      (node (ref "D2") (pin "C") (pinfunction "C_C") (pintype "passive"))
      (node (ref "D3") (pin "C") (pinfunction "C_C") (pintype "passive"))
      (node (ref "D4") (pin "C") (pinfunction "C_C") (pintype "passive"))
      (node (ref "D5") (pin "C") (pinfunction "C_C") (pintype "passive"))
      (node (ref "J1") (pin "3") (pinfunction "X-3_3") (pintype "bidirectional"))
      (node (ref "J10") (pin "1") (pinfunction "1_1") (pintype "passive"))
      (node (ref "J11") (pin "1") (pinfunction "1_1") (pintype "passive"))
      (node (ref "J12") (pin "1") (pinfunction "1_1") (pintype "passive"))
      (node (ref "J13") (pin "5") (pinfunction "5_5") (pintype "passive"))
      (node (ref "J14") (pin "5") (pinfunction "5_5") (pintype "passive"))
      (node (ref "J2") (pin "1") (pinfunction "1_1") (pintype "bidirectional"))
      (node (ref "J3") (pin "1") (pinfunction "1_1") (pintype "bidirectional"))
      (node (ref "J4") (pin "1") (pinfunction "1_1") (pintype "bidirectional"))
      (node (ref "J5") (pin "1") (pinfunction "1_1") (pintype "bidirectional"))
      (node (ref "J6") (pin "1") (pinfunction "1_1") (pintype "bidirectional"))
      (node (ref "R14") (pin "1") (pinfunction "1_1") (pintype "passive"))
      (node (ref "R5") (pin "2") (pinfunction "2_2") (pintype "passive"))
      (node (ref "R6") (pin "1") (pinfunction "1_1") (pintype "passive"))
      (node (ref "R7") (pin "1") (pinfunction "1_1") (pintype "passive"))
      (node (ref "R8") (pin "2") (pinfunction "2_2") (pintype "passive"))
      (node (ref "T1") (pin "2") (pinfunction "GND_2") (pintype "bidirectional"))
      (node (ref "U1") (pin "2") (pinfunction "IN_A_2") (pintype "bidirectional"))
      (node (ref "U1") (pin "3") (pinfunction "GND_3") (pintype "bidirectional"))
      (node (ref "U2") (pin "10") (pinfunction "B6_10") (pintype "bidirectional"))
      (node (ref "U2") (pin "2") (pinfunction "VCCA_2") (pintype "power_in"))
      (node (ref "U2") (pin "7") (pinfunction "A6_7") (pintype "bidirectional"))
      (node (ref "U2") (pin "9") (pinfunction "GND_9") (pintype "power_in"))
      (node (ref "U3") (pin "2") (pinfunction "GND_2") (pintype "power_in"))
      (node (ref "U4") (pin "2") (pinfunction "GND_2") (pintype "bidirectional"))
      (node (ref "U5") (pin "2") (pinfunction "VSS_2") (pintype "passive"))
      (node (ref "U5") (pin "8") (pinfunction "RS_8") (pintype "passive"))
      (node (ref "U6") (pin "2") (pinfunction "EPAD_2") (pintype "passive"))
      (node (ref "U7") (pin "2") (pinfunction "GND_2") (pintype "power_in"))
      (node (ref "X7") (pin "S1") (pinfunction "S1_S1") (pintype "passive"))
      (node (ref "X7") (pin "S2") (pinfunction "S2_S2") (pintype "passive"))
    )
    (net (code "16") (name "INDICATOR_LED") (class "Default")
      (node (ref "A1") (pin "12") (pinfunction "P$12_12") (pintype "bidirectional"))
      (node (ref "R1") (pin "2") (pinfunction "2_2") (pintype "passive"))
    )
    (net (code "17") (name "INT1_ACCEL") (class "Default")
      (node (ref "A1") (pin "5") (pinfunction "P$5_5") (pintype "bidirectional"))
    )
    (net (code "18") (name "INT2_ACCEL") (class "Default")
      (node (ref "A1") (pin "6") (pinfunction "P$6_6") (pintype "bidirectional"))
    )
    (net (code "19") (name "INT3_GYRO") (class "Default")
      (node (ref "A1") (pin "7") (pinfunction "P$7_7") (pintype "bidirectional"))
    )
    (net (code "20") (name "INT4_GYRO") (class "Default")
      (node (ref "A1") (pin "8") (pinfunction "P$8_8") (pintype "bidirectional"))
    )
    (net (code "21") (name "LEA") (class "Default")
      (node (ref "A1") (pin "24") (pinfunction "P$24_24") (pintype "bidirectional"))
      (node (ref "J13") (pin "3") (pinfunction "3_3") (pintype "passive"))
    )
    (net (code "22") (name "LEB") (class "Default")
      (node (ref "A1") (pin "23") (pinfunction "P$23_23") (pintype "bidirectional"))
      (node (ref "J13") (pin "1") (pinfunction "1_1") (pintype "passive"))
    )
    (net (code "23") (name "LIDAR_EN_1_3V3") (class "Default")
      (node (ref "A1") (pin "16") (pinfunction "P$16_16") (pintype "bidirectional"))
      (node (ref "U2") (pin "4") (pinfunction "A3_4") (pintype "bidirectional"))
    )
    (net (code "24") (name "LIDAR_EN_1_5V") (class "Default")
      (node (ref "J12") (pin "5") (pinfunction "5_5") (pintype "passive"))
      (node (ref "R8") (pin "1") (pinfunction "1_1") (pintype "passive"))
      (node (ref "U2") (pin "13") (pinfunction "B3_13") (pintype "bidirectional"))
    )
    (net (code "25") (name "LIDAR_EN_2_3V3") (class "Default")
      (node (ref "A1") (pin "17") (pinfunction "P$17_17") (pintype "bidirectional"))
      (node (ref "U2") (pin "3") (pinfunction "A2_3") (pintype "bidirectional"))
    )
    (net (code "26") (name "LIDAR_EN_2_5V") (class "Default")
      (node (ref "J11") (pin "5") (pinfunction "5_5") (pintype "passive"))
      (node (ref "R6") (pin "2") (pinfunction "2_2") (pintype "passive"))
      (node (ref "U2") (pin "14") (pinfunction "B2_14") (pintype "bidirectional"))
    )
    (net (code "27") (name "LIDAR_EN_3_3V3") (class "Default")
      (node (ref "A1") (pin "18") (pinfunction "P$18_18") (pintype "bidirectional"))
      (node (ref "U2") (pin "1") (pinfunction "A1_1") (pintype "bidirectional"))
    )
    (net (code "28") (name "LIDAR_EN_3_5V") (class "Default")
      (node (ref "J10") (pin "5") (pinfunction "5_5") (pintype "passive"))
      (node (ref "R7") (pin "2") (pinfunction "2_2") (pintype "passive"))
      (node (ref "U2") (pin "16") (pinfunction "B1_16") (pintype "bidirectional"))
    )
    (net (code "29") (name "LVL_SHIFT_OE") (class "Default")
      (node (ref "A1") (pin "14") (pinfunction "P$14_14") (pintype "bidirectional"))
      (node (ref "R5") (pin "1") (pinfunction "1_1") (pintype "passive"))
      (node (ref "U2") (pin "8") (pinfunction "OE_8") (pintype "output"))
    )
    (net (code "30") (name "MBED_CAN_RD") (class "Default")
      (node (ref "A1") (pin "30") (pinfunction "P$30_30") (pintype "bidirectional"))
      (node (ref "U5") (pin "1") (pinfunction "TXD_1") (pintype "passive"))
    )
    (net (code "31") (name "MBED_CAN_TD") (class "Default")
      (node (ref "A1") (pin "29") (pinfunction "P$29_29") (pintype "bidirectional"))
      (node (ref "U5") (pin "4") (pinfunction "RXD_4") (pintype "passive"))
    )
    (net (code "32") (name "MOTOR_CTRL") (class "Default")
      (node (ref "A1") (pin "13") (pinfunction "P$13_13") (pintype "bidirectional"))
      (node (ref "J6") (pin "2") (pinfunction "2_2") (pintype "bidirectional"))
    )
    (net (code "33") (name "NR") (class "Default")
      (node (ref "A1") (pin "4") (pinfunction "P$4_4") (pintype "bidirectional"))
      (node (ref "J7") (pin "2") (pinfunction "2_2") (pintype "bidirectional"))
      (node (ref "R2") (pin "1") (pinfunction "1_1") (pintype "passive"))
    )
    (net (code "34") (name "Net-(C3-Pad1)") (class "Default")
      (node (ref "C3") (pin "1") (pinfunction "1_1") (pintype "passive"))
      (node (ref "J7") (pin "1") (pinfunction "1_1") (pintype "bidirectional"))
    )
    (net (code "35") (name "Net-(D1-PadA)") (class "Default")
      (node (ref "D1") (pin "A") (pinfunction "A_A") (pintype "passive"))
      (node (ref "R1") (pin "1") (pinfunction "1_1") (pintype "passive"))
    )
    (net (code "36") (name "Net-(D2-PadA)") (class "Default")
      (node (ref "D2") (pin "A") (pinfunction "A_A") (pintype "passive"))
      (node (ref "R12") (pin "1") (pinfunction "1_1") (pintype "passive"))
    )
    (net (code "37") (name "Net-(D3-PadA)") (class "Default")
      (node (ref "D3") (pin "A") (pinfunction "A_A") (pintype "passive"))
      (node (ref "R18") (pin "1") (pinfunction "1_1") (pintype "passive"))
    )
    (net (code "38") (name "Net-(D4-PadA)") (class "Default")
      (node (ref "D4") (pin "A") (pinfunction "A_A") (pintype "passive"))
      (node (ref "R19") (pin "1") (pinfunction "1_1") (pintype "passive"))
    )
    (net (code "39") (name "Net-(D5-PadA)") (class "Default")
      (node (ref "D5") (pin "A") (pinfunction "A_A") (pintype "passive"))
      (node (ref "R21") (pin "1") (pinfunction "1_1") (pintype "passive"))
    )
    (net (code "40") (name "Net-(J2-Pad2)") (class "Default")
      (node (ref "J2") (pin "2") (pinfunction "2_2") (pintype "bidirectional"))
      (node (ref "Q4") (pin "1") (pinfunction "D_1") (pintype "passive"))
      (node (ref "Q4") (pin "2") (pinfunction "D_2") (pintype "passive"))
      (node (ref "Q4") (pin "5") (pinfunction "D_5") (pintype "passive"))
      (node (ref "Q4") (pin "6") (pinfunction "D_6") (pintype "passive"))
    )
    (net (code "41") (name "Net-(Q4-G)") (class "Default")
      (node (ref "Q4") (pin "3") (pinfunction "G_3") (pintype "passive"))
      (node (ref "R25") (pin "2") (pinfunction "2_2") (pintype "passive"))
    )
    (net (code "42") (name "RD_N") (class "Default")
      (node (ref "A1") (pin "36") (pinfunction "P$36_36") (pintype "bidirectional"))
      (node (ref "X7") (pin "6") (pinfunction "RD-_6") (pintype "passive"))
    )
    (net (code "43") (name "RD_P") (class "Default")
      (node (ref "A1") (pin "35") (pinfunction "P$35_35") (pintype "bidirectional"))
      (node (ref "X7") (pin "4") (pinfunction "RD+_4") (pintype "passive"))
    )
    (net (code "44") (name "REA") (class "Default")
      (node (ref "A1") (pin "26") (pinfunction "P$26_26") (pintype "bidirectional"))
      (node (ref "J14") (pin "3") (pinfunction "3_3") (pintype "passive"))
    )
    (net (code "45") (name "REB") (class "Default")
      (node (ref "A1") (pin "25") (pinfunction "P$25_25") (pintype "bidirectional"))
      (node (ref "J14") (pin "1") (pinfunction "1_1") (pintype "passive"))
    )
    (net (code "46") (name "SAFETY_LIGHT") (class "Default")
      (node (ref "R25") (pin "1") (pinfunction "1_1") (pintype "passive"))
      (node (ref "U1") (pin "5") (pinfunction "~{OUT_B}_5") (pintype "bidirectional"))
    )
    (net (code "47") (name "SAFETY_LIGHT_3V3") (class "Default")
      (node (ref "A1") (pin "11") (pinfunction "P$11_11") (pintype "bidirectional"))
      (node (ref "U1") (pin "4") (pinfunction "IN_B_4") (pintype "bidirectional"))
    )
    (net (code "48") (name "SCL_3V3") (class "Default")
      (node (ref "A1") (pin "10") (pinfunction "P$10_10") (pintype "bidirectional"))
      (node (ref "U2") (pin "5") (pinfunction "A4_5") (pintype "bidirectional"))
    )
    (net (code "49") (name "SCL_5V") (class "Default")
      (node (ref "C14") (pin "1") (pinfunction "1_1") (pintype "passive"))
      (node (ref "J10") (pin "3") (pinfunction "3_3") (pintype "passive"))
      (node (ref "J11") (pin "3") (pinfunction "3_3") (pintype "passive"))
      (node (ref "J12") (pin "3") (pinfunction "3_3") (pintype "passive"))
      (node (ref "R4") (pin "1") (pinfunction "1_1") (pintype "passive"))
      (node (ref "U2") (pin "12") (pinfunction "B4_12") (pintype "bidirectional"))
    )
    (net (code "50") (name "SDA_3V3") (class "Default")
      (node (ref "A1") (pin "9") (pinfunction "P$9_9") (pintype "bidirectional"))
      (node (ref "U2") (pin "6") (pinfunction "A5_6") (pintype "bidirectional"))
    )
    (net (code "51") (name "SDA_5V") (class "Default")
      (node (ref "C15") (pin "1") (pinfunction "1_1") (pintype "passive"))
      (node (ref "J10") (pin "2") (pinfunction "2_2") (pintype "passive"))
      (node (ref "J11") (pin "2") (pinfunction "2_2") (pintype "passive"))
      (node (ref "J12") (pin "2") (pinfunction "2_2") (pintype "passive"))
      (node (ref "R3") (pin "1") (pinfunction "1_1") (pintype "passive"))
      (node (ref "U2") (pin "11") (pinfunction "B5_11") (pintype "bidirectional"))
    )
    (net (code "52") (name "STATUS_LED1") (class "Default")
      (node (ref "A1") (pin "32") (pinfunction "P$32_32") (pintype "bidirectional"))
      (node (ref "J8") (pin "2") (pinfunction "2_2") (pintype "bidirectional"))
    )
    (net (code "53") (name "STATUS_LED2") (class "Default")
      (node (ref "A1") (pin "31") (pinfunction "P$31_31") (pintype "bidirectional"))
      (node (ref "J8") (pin "1") (pinfunction "1_1") (pintype "bidirectional"))
    )
    (net (code "54") (name "TD_N") (class "Default")
      (node (ref "A1") (pin "34") (pinfunction "P$34_34") (pintype "bidirectional"))
      (node (ref "X7") (pin "3") (pinfunction "TD-_3") (pintype "passive"))
    )
    (net (code "55") (name "TD_P") (class "Default")
      (node (ref "A1") (pin "33") (pinfunction "P$33_33") (pintype "bidirectional"))
      (node (ref "X7") (pin "1") (pinfunction "TD+_1") (pintype "passive"))
    )
    (net (code "56") (name "unconnected-(A1-P$3-Pad3)") (class "Default")
      (node (ref "A1") (pin "3") (pinfunction "P$3_3") (pintype "bidirectional"))
    )
    (net (code "57") (name "unconnected-(A1-P$20-Pad20)") (class "Default")
      (node (ref "A1") (pin "20") (pinfunction "P$20_20") (pintype "bidirectional"))
    )
    (net (code "58") (name "unconnected-(A1-P$21-Pad21)") (class "Default")
      (node (ref "A1") (pin "21") (pinfunction "P$21_21") (pintype "bidirectional"))
    )
    (net (code "59") (name "unconnected-(A1-P$22-Pad22)") (class "Default")
      (node (ref "A1") (pin "22") (pinfunction "P$22_22") (pintype "bidirectional"))
    )
    (net (code "60") (name "unconnected-(A1-P$37-Pad37)") (class "Default")
      (node (ref "A1") (pin "37") (pinfunction "P$37_37") (pintype "bidirectional"))
    )
    (net (code "61") (name "unconnected-(A1-P$38-Pad38)") (class "Default")
      (node (ref "A1") (pin "38") (pinfunction "P$38_38") (pintype "bidirectional"))
    )
    (net (code "62") (name "unconnected-(A1-P$39-Pad39)") (class "Default")
      (node (ref "A1") (pin "39") (pinfunction "P$39_39") (pintype "bidirectional"))
    )
    (net (code "63") (name "unconnected-(A1-P$40-Pad40)") (class "Default")
      (node (ref "A1") (pin "40") (pinfunction "P$40_40") (pintype "bidirectional"))
    )
    (net (code "64") (name "unconnected-(J1-X-2-Pad2)") (class "Default")
      (node (ref "J1") (pin "2") (pinfunction "X-2_2") (pintype "bidirectional"))
    )
    (net (code "65") (name "unconnected-(J10-Pad4)") (class "Default")
      (node (ref "J10") (pin "4") (pinfunction "4_4") (pintype "passive"))
    )
    (net (code "66") (name "unconnected-(J11-Pad4)") (class "Default")
      (node (ref "J11") (pin "4") (pinfunction "4_4") (pintype "passive"))
    )
    (net (code "67") (name "unconnected-(J12-Pad4)") (class "Default")
      (node (ref "J12") (pin "4") (pinfunction "4_4") (pintype "passive"))
    )
    (net (code "68") (name "unconnected-(J13-Pad4)") (class "Default")
      (node (ref "J13") (pin "4") (pinfunction "4_4") (pintype "passive"))
    )
    (net (code "69") (name "unconnected-(J14-Pad4)") (class "Default")
      (node (ref "J14") (pin "4") (pinfunction "4_4") (pintype "passive"))
    )
    (net (code "70") (name "unconnected-(U1-NC-Pad1)") (class "Default")
      (node (ref "U1") (pin "1") (pinfunction "NC_1") (pintype "bidirectional"))
    )
    (net (code "71") (name "unconnected-(U1-NC2-Pad8)") (class "Default")
      (node (ref "U1") (pin "8") (pinfunction "NC2_8") (pintype "bidirectional"))
    )
    (net (code "72") (name "unconnected-(U1-~{OUT_A}-Pad7)") (class "Default")
      (node (ref "U1") (pin "7") (pinfunction "~{OUT_A}_7") (pintype "bidirectional"))
    )
    (net (code "73") (name "unconnected-(U5-VREF-Pad5)") (class "Default")
      (node (ref "U5") (pin "5") (pinfunction "VREF_5") (pintype "passive"))
    )
    (net (code "74") (name "unconnected-(X7-A-PadA1)") (class "Default")
      (node (ref "X7") (pin "A1") (pinfunction "A_A1") (pintype "passive"))
    )
    (net (code "75") (name "unconnected-(X7-A1-PadA2)") (class "Default")
      (node (ref "X7") (pin "A2") (pinfunction "A1_A2") (pintype "passive"))
    )
    (net (code "76") (name "unconnected-(X7-C-PadC1)") (class "Default")
      (node (ref "X7") (pin "C1") (pinfunction "C_C1") (pintype "passive"))
    )
    (net (code "77") (name "unconnected-(X7-C1-PadC2)") (class "Default")
      (node (ref "X7") (pin "C2") (pinfunction "C1_C2") (pintype "passive"))
    )
    (net (code "78") (name "unconnected-(X7-C_GND-Pad8)") (class "Default")
      (node (ref "X7") (pin "8") (pinfunction "C_GND_8") (pintype "passive"))
    )
    (net (code "79") (name "unconnected-(X7-NC-Pad7)") (class "Default")
      (node (ref "X7") (pin "7") (pinfunction "NC_7") (pintype "passive"))
    )
  )
)
